# EasyEDA_Pro_Project_0_02.net
KiCad netlist of a schematic drawn in EasyEDA Pro
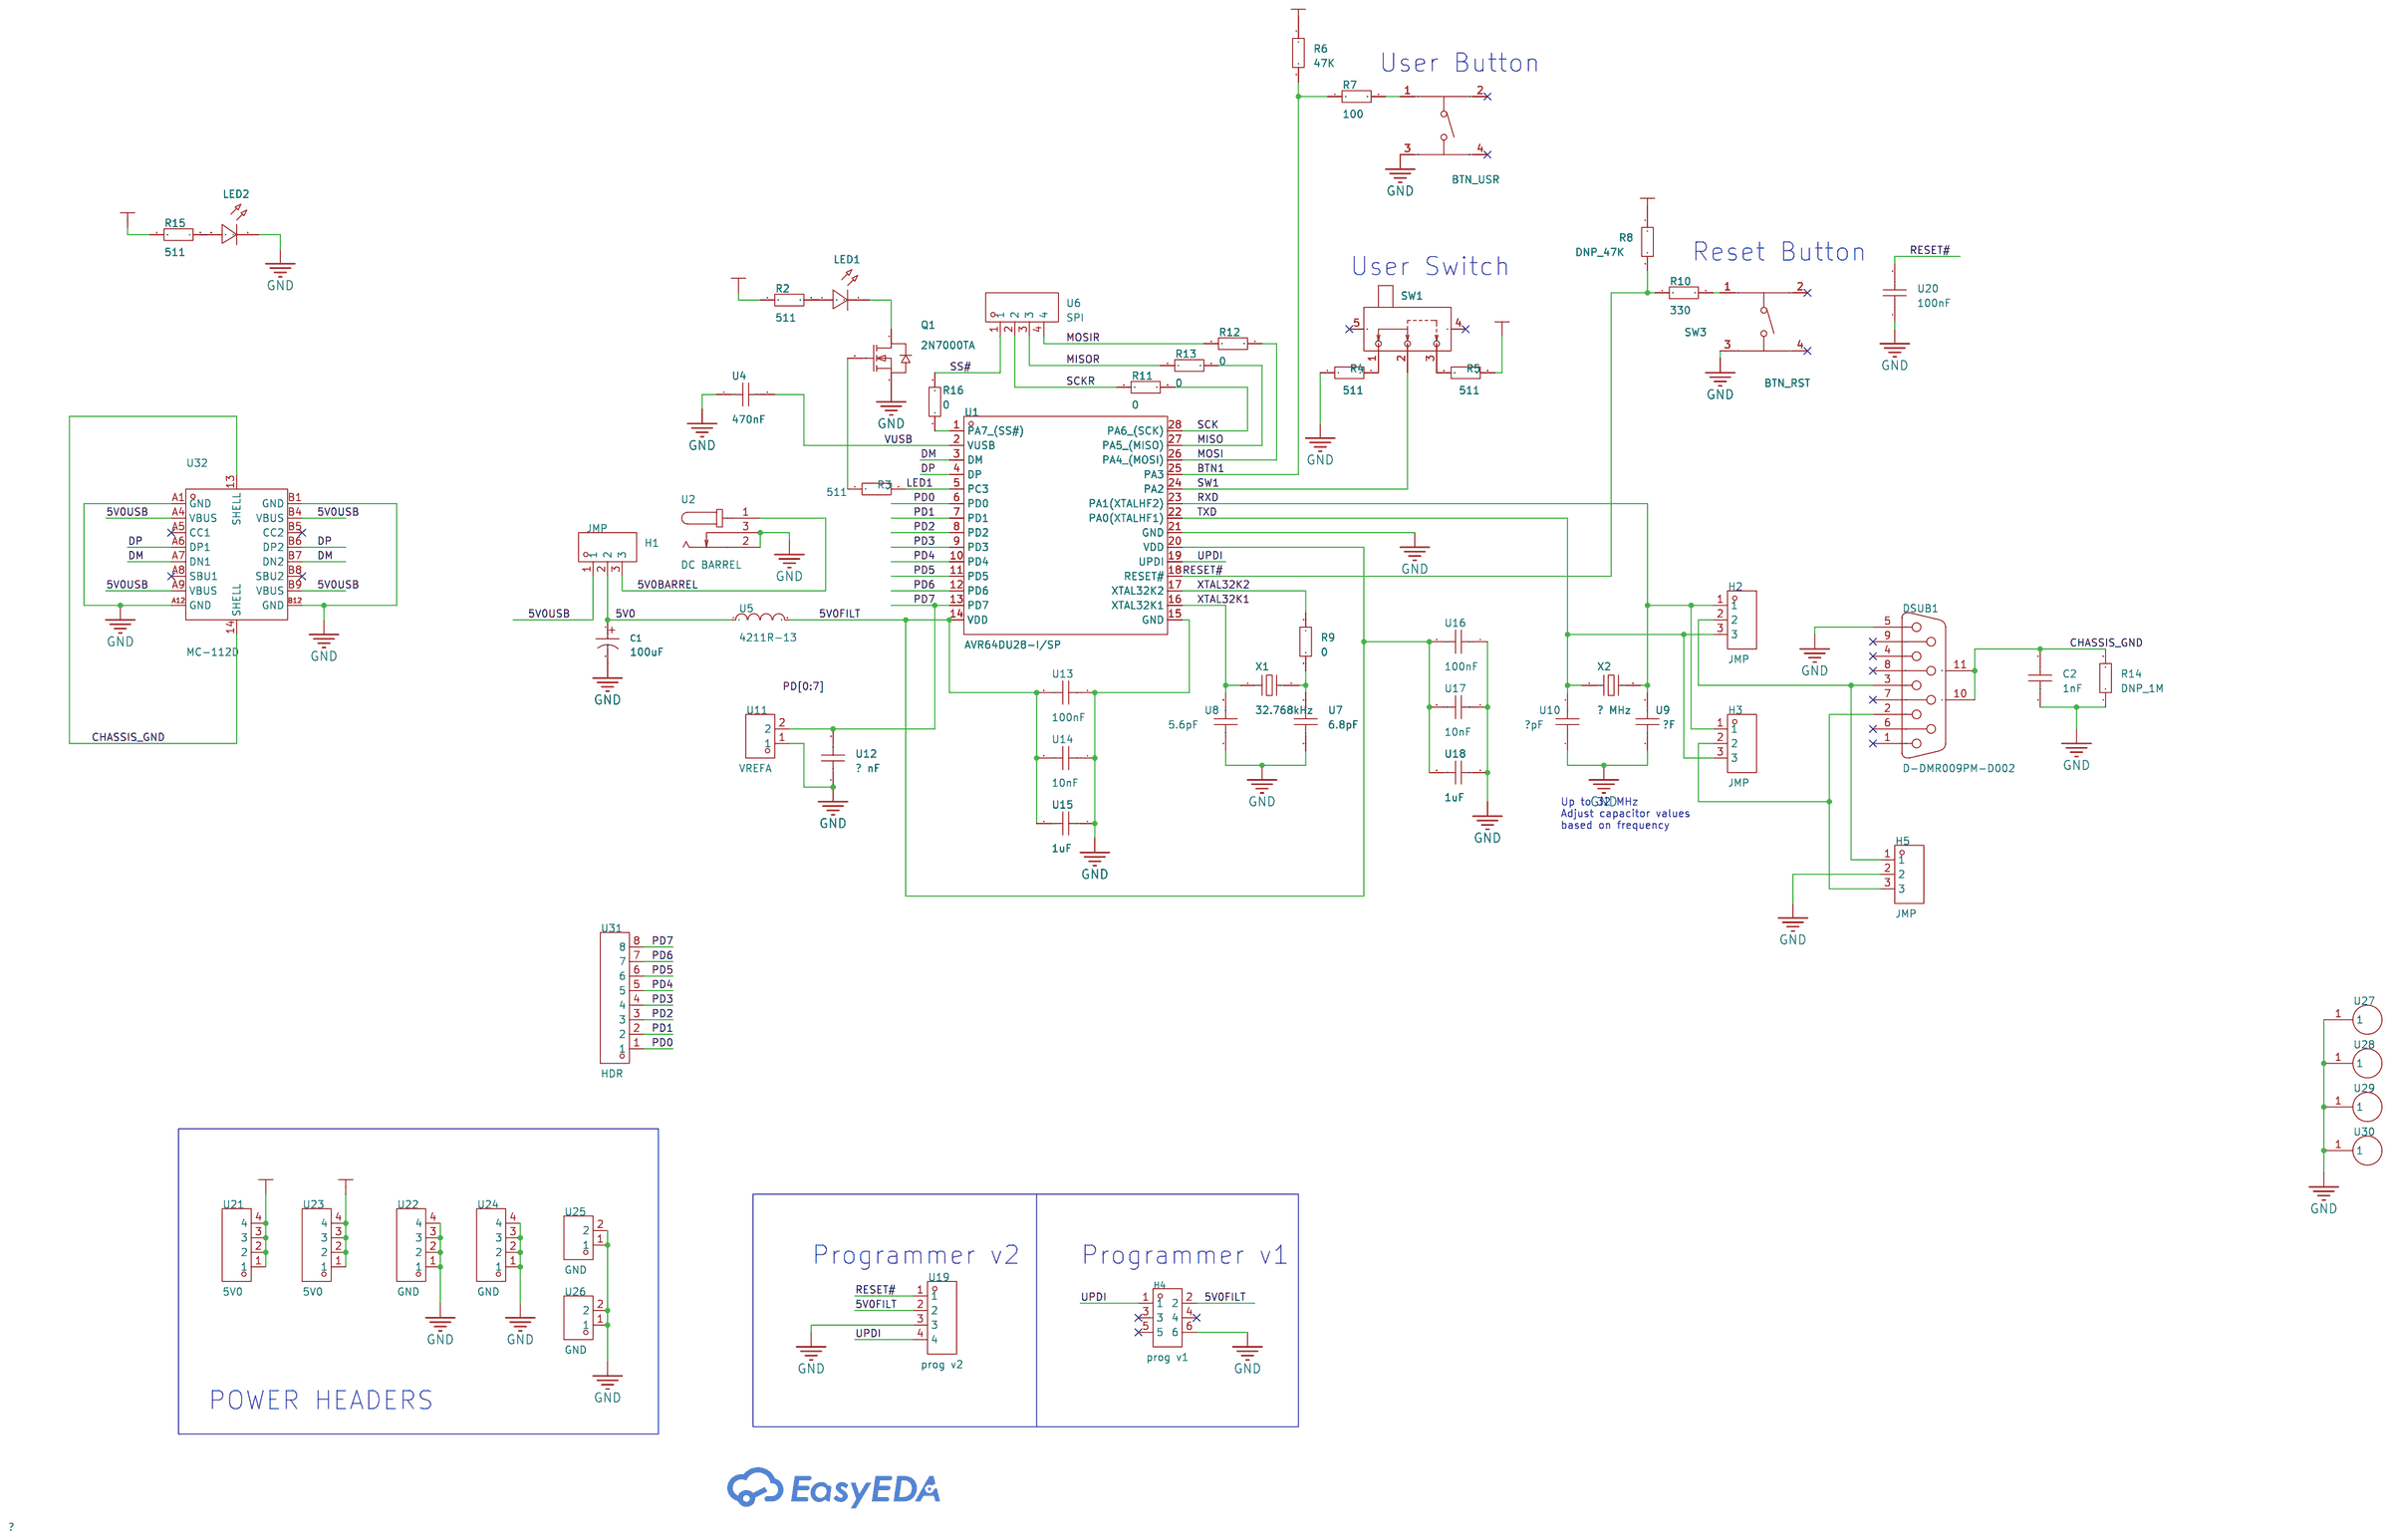
[diagram p0: schematic sheet]

(export (version "E")
  (design (tool "Eeschema 10.0.6"))
  (components
    (comp (ref "BTN_USR")
      (value "GT-TC075B-H070-L1")
      (footprint "easyedapro:KEY-TH_4P-L4.5-W4.5-P3.00-LS5.8")
      (fields (field (name "Manufacturer") "G-Switch(品赞)"))
      (libsource (lib "easyedapro") (part "GT-TC075B-H070-L1"))
    )
    (comp (ref "C1")
      (value "100uF")
      (footprint "easyedapro:CAP-TH_BD5.0-P2.00-D0.8-FD")
      (fields
        (field (name "Manufacturer Part") "KS107M010D07RR0VH2FP0")
        (field (name "Manufacturer") "CX(承兴)")
      )
      (libsource (lib "easyedapro") (part "100uF 10V 5*7"))
    )
    (comp (ref "C2")
      (value "1nF")
      (footprint "easyedapro:CAP-TH_L6.0-W3.5-P7.50-D1.0")
      (fields (field (name "Manufacturer Part") "Y25E1E102M") (field (name "Manufacturer") "HEL(鸿志)"))
      (libsource (lib "easyedapro") (part "Y25E1E102M"))
    )
    (comp (ref "DSUB1")
      (value "D-DMR009PM-D002")
      (footprint "easyedapro:DSUB-TH_DMR-9P")
      (fields (field (name "Manufacturer") "Ckmtw(灿科盟)"))
      (libsource (lib "easyedapro") (part "DMR-9P"))
    )
    (comp (ref "H1")
      (value "JMP")
      (footprint "easyedapro:HDR-TH_3P-P2.54-V-M-1")
      (fields (field (name "Manufacturer") "JILN(锦凌)"))
      (libsource (lib "easyedapro") (part "12251103CNG0S115001"))
    )
    (comp (ref "H2")
      (value "JMP")
      (footprint "easyedapro:HDR-TH_3P-P2.54-V-M-1")
      (fields (field (name "Manufacturer") "JILN(锦凌)"))
      (libsource (lib "easyedapro") (part "12251103CNG0S115001"))
    )
    (comp (ref "H3")
      (value "JMP")
      (footprint "easyedapro:HDR-TH_3P-P2.54-V-M-1")
      (fields (field (name "Manufacturer") "JILN(锦凌)"))
      (libsource (lib "easyedapro") (part "12251103CNG0S115001"))
    )
    (comp (ref "H4")
      (value "prog v1")
      (footprint "easyedapro:HDR-TH_6P-P2.54-V-M-R2-C3-S2.54")
      (fields (field (name "Manufacturer") "Liansheng(连盛)"))
      (libsource (lib "easyedapro") (part "PH-01291"))
    )
    (comp (ref "H5")
      (value "JMP")
      (footprint "easyedapro:HDR-TH_3P-P2.54-V-M-1")
      (fields (field (name "Manufacturer") "JILN(锦凌)"))
      (libsource (lib "easyedapro") (part "12251103CNG0S115001"))
    )
    (comp (ref "LED1")
      (value "~")
      (footprint "easyedapro:LED-TH_BD3.0-P2.54-FD")
      (libsource (lib "easyedapro") (part "LED_TH-R"))
    )
    (comp (ref "LED2")
      (value "~")
      (footprint "easyedapro:LED-TH_BD3.0-P2.54-FD")
      (libsource (lib "easyedapro") (part "LED_TH-R"))
    )
    (comp (ref "Q1")
      (value "2N7000TA")
      (footprint "easyedapro:TO-92-3_L4.8-W3.7-P2.54-L")
      (fields (field (name "Manufacturer") "onsemi(安森美)"))
      (libsource (lib "easyedapro") (part "2N7000TA"))
    )
    (comp (ref "R2")
      (value "511")
      (footprint "easyedapro:RES-TH_BD1.8-L3.2-P7.20-D0.4")
      (libsource (lib "easyedapro") (part "Res"))
    )
    (comp (ref "R3")
      (value "511")
      (footprint "easyedapro:RES-TH_BD1.8-L3.2-P7.20-D0.4")
      (libsource (lib "easyedapro") (part "Res"))
    )
    (comp (ref "R4")
      (value "511")
      (footprint "easyedapro:RES-TH_BD1.8-L3.2-P7.20-D0.4")
      (libsource (lib "easyedapro") (part "Res"))
    )
    (comp (ref "R5")
      (value "511")
      (footprint "easyedapro:RES-TH_BD1.8-L3.2-P7.20-D0.4")
      (libsource (lib "easyedapro") (part "Res"))
    )
    (comp (ref "R6")
      (value "47K")
      (footprint "easyedapro:RES-TH_BD1.8-L3.2-P7.20-D0.4")
      (libsource (lib "easyedapro") (part "Res"))
    )
    (comp (ref "R7")
      (value "100")
      (footprint "easyedapro:RES-TH_BD1.8-L3.2-P7.20-D0.4")
      (libsource (lib "easyedapro") (part "Res"))
    )
    (comp (ref "R8")
      (value "DNP_47K")
      (footprint "easyedapro:RES-TH_BD1.8-L3.2-P7.20-D0.4")
      (libsource (lib "easyedapro") (part "Res"))
    )
    (comp (ref "R9")
      (value "0")
      (footprint "easyedapro:RES-TH_BD1.8-L3.2-P7.20-D0.4")
      (libsource (lib "easyedapro") (part "Res"))
    )
    (comp (ref "R10")
      (value "330")
      (footprint "easyedapro:RES-TH_BD1.8-L3.2-P7.20-D0.4")
      (libsource (lib "easyedapro") (part "Res"))
    )
    (comp (ref "R11")
      (value "0")
      (footprint "easyedapro:RES-TH_BD1.8-L3.2-P7.20-D0.4")
      (libsource (lib "easyedapro") (part "Res"))
    )
    (comp (ref "R12")
      (value "0")
      (footprint "easyedapro:RES-TH_BD1.8-L3.2-P7.20-D0.4")
      (libsource (lib "easyedapro") (part "Res"))
    )
    (comp (ref "R13")
      (value "0")
      (footprint "easyedapro:RES-TH_BD1.8-L3.2-P7.20-D0.4")
      (libsource (lib "easyedapro") (part "Res"))
    )
    (comp (ref "R14")
      (value "DNP_1M")
      (footprint "easyedapro:RES-TH_BD1.8-L3.2-P7.20-D0.4")
      (libsource (lib "easyedapro") (part "Res"))
    )
    (comp (ref "R15")
      (value "511")
      (footprint "easyedapro:RES-TH_BD1.8-L3.2-P7.20-D0.4")
      (libsource (lib "easyedapro") (part "Res"))
    )
    (comp (ref "R16")
      (value "0")
      (footprint "easyedapro:RES-TH_BD1.8-L3.2-P7.20-D0.4")
      (libsource (lib "easyedapro") (part "Res"))
    )
    (comp (ref "SW1")
      (value "SS-12D07G4")
      (footprint "easyedapro:SW-TH_DEALON_SS-12D02-VGX")
      (fields (field (name "Manufacturer") "HanElectricity(瀚源)"))
      (libsource (lib "easyedapro") (part "SS-12D07G4"))
    )
    (comp (ref "SW3")
      (value "BTN_RST")
      (footprint "easyedapro:KEY-TH_4P-L4.5-W4.5-P3.00-LS5.8")
      (fields (field (name "Manufacturer") "G-Switch(品赞)"))
      (libsource (lib "easyedapro") (part "GT-TC075B-H070-L1"))
    )
    (comp (ref "U1")
      (value "AVR64DU28-I/SP")
      (footprint "easyedapro:SPDIP-28_L34.7-W7.2-P2.54-LS7.9-BL")
      (fields (field (name "Manufacturer") "MICROCHIP(美国微芯)"))
      (libsource (lib "easyedapro") (part "AVR64DB28-I/SP"))
    )
    (comp (ref "U2")
      (value "DC BARREL")
      (footprint "easyedapro:DC-IN-TH_DC-005-2.0_C22459640")
      (fields (field (name "Manufacturer") "HanElectricity(瀚源)"))
      (libsource (lib "easyedapro") (part "DC-005-2.0_C22459640"))
    )
    (comp (ref "U4")
      (value "470nF")
      (footprint "easyedapro:CAP-TH_L4.8-W2.4-P5.08-D0.6")
      (fields (field (name "Manufacturer Part") "178MU0009") (field (name "Manufacturer") "KNSCHA(科尼盛)"))
      (libsource (lib "easyedapro") (part "178MU0009"))
    )
    (comp (ref "U5")
      (value "4211R-13")
      (footprint "easyedapro:IND-TH_BD3.5-L4.4_4211R-13")
      (description "Impedance @ Frequency:50Ω@100MHz Circuits:1")
      (fields (field (name "Manufacturer") "API Delevan"))
      (libsource (lib "easyedapro") (part "4211R-13"))
    )
    (comp (ref "U6")
      (value "SPI")
      (footprint "easyedapro:HDR-TH_4P-P2.00-V-M")
      (fields (field (name "Manufacturer") "Yxcon(宇熙精密)"))
      (libsource (lib "easyedapro") (part "P220-1104A0BS087A1"))
    )
    (comp (ref "U7")
      (value "6.8pF")
      (footprint "easyedapro:CAP-TH_L4.8-W2.4-P5.08-D0.6")
      (fields (field (name "Manufacturer Part") "178MU0009") (field (name "Manufacturer") "KNSCHA(科尼盛)"))
      (libsource (lib "easyedapro") (part "178MU0009"))
    )
    (comp (ref "U8")
      (value "5.6pF")
      (footprint "easyedapro:CAP-TH_L4.8-W2.4-P5.08-D0.6")
      (fields (field (name "Manufacturer Part") "178MU0009") (field (name "Manufacturer") "KNSCHA(科尼盛)"))
      (libsource (lib "easyedapro") (part "178MU0009"))
    )
    (comp (ref "U9")
      (value "?F")
      (footprint "easyedapro:CAP-TH_L4.8-W2.4-P5.08-D0.6")
      (fields (field (name "Manufacturer Part") "178MU0009") (field (name "Manufacturer") "KNSCHA(科尼盛)"))
      (libsource (lib "easyedapro") (part "178MU0009"))
    )
    (comp (ref "U10")
      (value "?pF")
      (footprint "easyedapro:CAP-TH_L4.8-W2.4-P5.08-D0.6")
      (fields (field (name "Manufacturer Part") "178MU0009") (field (name "Manufacturer") "KNSCHA(科尼盛)"))
      (libsource (lib "easyedapro") (part "178MU0009"))
    )
    (comp (ref "U11")
      (value "VREFA")
      (footprint "easyedapro:HDR-TH_2P-P2.00-V-M")
      (fields (field (name "Manufacturer") "hanxia(韩下)"))
      (libsource (lib "easyedapro") (part "HX PZ2.0-1X2P ZZ"))
    )
    (comp (ref "U12")
      (value "? nF")
      (footprint "easyedapro:CAP-TH_L4.8-W2.4-P5.08-D0.6")
      (fields (field (name "Manufacturer Part") "178MU0009") (field (name "Manufacturer") "KNSCHA(科尼盛)"))
      (libsource (lib "easyedapro") (part "178MU0009"))
    )
    (comp (ref "U13")
      (value "100nF")
      (footprint "easyedapro:CAP-TH_L4.8-W2.4-P5.08-D0.6")
      (fields (field (name "Manufacturer Part") "178MU0009") (field (name "Manufacturer") "KNSCHA(科尼盛)"))
      (libsource (lib "easyedapro") (part "178MU0009"))
    )
    (comp (ref "U14")
      (value "10nF")
      (footprint "easyedapro:CAP-TH_L4.8-W2.4-P5.08-D0.6")
      (fields (field (name "Manufacturer Part") "178MU0009") (field (name "Manufacturer") "KNSCHA(科尼盛)"))
      (libsource (lib "easyedapro") (part "178MU0009"))
    )
    (comp (ref "U15")
      (value "1uF")
      (footprint "easyedapro:CAP-TH_L4.8-W2.4-P5.08-D0.6")
      (fields (field (name "Manufacturer Part") "178MU0009") (field (name "Manufacturer") "KNSCHA(科尼盛)"))
      (libsource (lib "easyedapro") (part "178MU0009"))
    )
    (comp (ref "U16")
      (value "100nF")
      (footprint "easyedapro:CAP-TH_L4.8-W2.4-P5.08-D0.6")
      (fields (field (name "Manufacturer Part") "178MU0009") (field (name "Manufacturer") "KNSCHA(科尼盛)"))
      (libsource (lib "easyedapro") (part "178MU0009"))
    )
    (comp (ref "U17")
      (value "10nF")
      (footprint "easyedapro:CAP-TH_L4.8-W2.4-P5.08-D0.6")
      (fields (field (name "Manufacturer Part") "178MU0009") (field (name "Manufacturer") "KNSCHA(科尼盛)"))
      (libsource (lib "easyedapro") (part "178MU0009"))
    )
    (comp (ref "U18")
      (value "1uF")
      (footprint "easyedapro:CAP-TH_L4.8-W2.4-P5.08-D0.6")
      (fields (field (name "Manufacturer Part") "178MU0009") (field (name "Manufacturer") "KNSCHA(科尼盛)"))
      (libsource (lib "easyedapro") (part "178MU0009"))
    )
    (comp (ref "U19")
      (value "prog v2")
      (footprint "easyedapro:HDR-TH_4P-P2.00-V-M")
      (fields (field (name "Manufacturer") "Yxcon(宇熙精密)"))
      (libsource (lib "easyedapro") (part "P220-1104A0BS087A1"))
    )
    (comp (ref "U20")
      (value "100nF")
      (footprint "easyedapro:CAP-TH_L4.8-W2.4-P5.08-D0.6")
      (fields (field (name "Manufacturer Part") "178MU0009") (field (name "Manufacturer") "KNSCHA(科尼盛)"))
      (libsource (lib "easyedapro") (part "178MU0009"))
    )
    (comp (ref "U21")
      (value "5V0")
      (footprint "easyedapro:HDR-TH_4P-P2.00-V-M")
      (fields (field (name "Manufacturer") "Yxcon(宇熙精密)"))
      (libsource (lib "easyedapro") (part "P220-1104A0BS087A1"))
    )
    (comp (ref "U22")
      (value "GND")
      (footprint "easyedapro:HDR-TH_4P-P2.00-V-M")
      (fields (field (name "Manufacturer") "Yxcon(宇熙精密)"))
      (libsource (lib "easyedapro") (part "P220-1104A0BS087A1"))
    )
    (comp (ref "U23")
      (value "5V0")
      (footprint "easyedapro:HDR-TH_4P-P2.00-V-M")
      (fields (field (name "Manufacturer") "Yxcon(宇熙精密)"))
      (libsource (lib "easyedapro") (part "P220-1104A0BS087A1"))
    )
    (comp (ref "U24")
      (value "GND")
      (footprint "easyedapro:HDR-TH_4P-P2.00-V-M")
      (fields (field (name "Manufacturer") "Yxcon(宇熙精密)"))
      (libsource (lib "easyedapro") (part "P220-1104A0BS087A1"))
    )
    (comp (ref "U25")
      (value "GND")
      (footprint "easyedapro:HDR-TH_2P-P2.00-V-M")
      (fields (field (name "Manufacturer") "hanxia(韩下)"))
      (libsource (lib "easyedapro") (part "HX PZ2.0-1X2P ZZ"))
    )
    (comp (ref "U26")
      (value "GND")
      (footprint "easyedapro:HDR-TH_2P-P2.00-V-M")
      (fields (field (name "Manufacturer") "hanxia(韩下)"))
      (libsource (lib "easyedapro") (part "HX PZ2.0-1X2P ZZ"))
    )
    (comp (ref "U27")
      (value "~")
      (footprint "easyedapro:Standoff 2.0mm")
      (libsource (lib "easyedapro") (part "Standoff 2.0mm"))
    )
    (comp (ref "U28")
      (value "~")
      (footprint "easyedapro:Standoff 2.0mm")
      (libsource (lib "easyedapro") (part "Standoff 2.0mm"))
    )
    (comp (ref "U29")
      (value "~")
      (footprint "easyedapro:Standoff 2.0mm")
      (libsource (lib "easyedapro") (part "Standoff 2.0mm"))
    )
    (comp (ref "U30")
      (value "~")
      (footprint "easyedapro:Standoff 2.0mm")
      (libsource (lib "easyedapro") (part "Standoff 2.0mm"))
    )
    (comp (ref "U31")
      (value "HDR")
      (footprint "easyedapro:HDR-TH_8P-P2.54-V-M")
      (fields (field (name "Manufacturer") "HANBO(汉博)"))
      (libsource (lib "easyedapro") (part "HB-PH3-25418PB2GOP"))
    )
    (comp (ref "U32")
      (value "MC-112D")
      (footprint "easyedapro:USB-C-TH_HANBO_MC-112D")
      (fields (field (name "Manufacturer") "HANBO(汉博)"))
      (libsource (lib "easyedapro") (part "MC-112D"))
    )
    (comp (ref "X1")
      (value "32.768kHz")
      (footprint "easyedapro:OSC-TH_BD2.0-P0.70-D0.3")
      (fields
        (field (name "Manufacturer Part") "TAXD32768K2BGBBZT2S")
        (field (name "Manufacturer") "YJX(雅晶鑫)")
      )
      (libsource (lib "easyedapro") (part "TAXD32768K2BGBBZT2S"))
    )
    (comp (ref "X2")
      (value "? MHz")
      (footprint "easyedapro:OSC-TH_BD2.0-P0.70-D0.3")
      (fields
        (field (name "Manufacturer Part") "TAXD32768K2BGBBZT2S")
        (field (name "Manufacturer") "YJX(雅晶鑫)")
      )
      (libsource (lib "easyedapro") (part "TAXD32768K2BGBBZT2S"))
    )
  )
  (nets
    (net (code "1") (name "/5V0BARREL") (class "Default")
      (node (ref "H1") (pin "3") (pinfunction "3_3") (pintype "unspecified"))
      (node (ref "U2") (pin "1") (pinfunction "1_1") (pintype "unspecified"))
    )
    (net (code "2") (name "/5V0FILT") (class "Default")
      (node (ref "H4") (pin "2") (pinfunction "2_2") (pintype "input"))
      (node (ref "U1") (pin "14") (pinfunction "VDD_14") (pintype "unspecified"))
      (node (ref "U1") (pin "20") (pinfunction "VDD_20") (pintype "unspecified"))
      (node (ref "U13") (pin "2") (pinfunction "2_2") (pintype "unspecified"))
      (node (ref "U14") (pin "2") (pinfunction "2_2") (pintype "unspecified"))
      (node (ref "U15") (pin "2") (pinfunction "2_2") (pintype "unspecified"))
      (node (ref "U16") (pin "2") (pinfunction "2_2") (pintype "unspecified"))
      (node (ref "U17") (pin "2") (pinfunction "2_2") (pintype "unspecified"))
      (node (ref "U18") (pin "2") (pinfunction "2_2") (pintype "unspecified"))
      (node (ref "U19") (pin "2") (pinfunction "2_2") (pintype "unspecified"))
      (node (ref "U5") (pin "2") (pinfunction "2_2") (pintype "unspecified"))
    )
    (net (code "3") (name "/5V0USB") (class "Default")
      (node (ref "H1") (pin "1") (pinfunction "1_1") (pintype "unspecified"))
      (node (ref "U32") (pin "A4") (pinfunction "VBUS_A4") (pintype "unspecified"))
      (node (ref "U32") (pin "A9") (pinfunction "VBUS_A9") (pintype "unspecified"))
      (node (ref "U32") (pin "B4") (pinfunction "VBUS_B4") (pintype "unspecified"))
      (node (ref "U32") (pin "B9") (pinfunction "VBUS_B9") (pintype "unspecified"))
    )
    (net (code "4") (name "/BTN1") (class "Default")
      (node (ref "R6") (pin "2") (pinfunction "2_2") (pintype "input"))
      (node (ref "R7") (pin "1") (pinfunction "1_1") (pintype "input"))
      (node (ref "U1") (pin "25") (pinfunction "PA3_25") (pintype "unspecified"))
    )
    (net (code "5") (name "/CHASSIS_GND") (class "Default")
      (node (ref "C2") (pin "1") (pinfunction "1_1") (pintype "input"))
      (node (ref "DSUB1") (pin "10") (pinfunction "MH1_10") (pintype "input"))
      (node (ref "DSUB1") (pin "11") (pinfunction "MH2_11") (pintype "input"))
      (node (ref "R14") (pin "2") (pinfunction "2_2") (pintype "input"))
      (node (ref "U32") (pin "13") (pinfunction "SHELL_13") (pintype "unspecified"))
      (node (ref "U32") (pin "14") (pinfunction "SHELL_14") (pintype "unspecified"))
    )
    (net (code "6") (name "/DM") (class "Default")
      (node (ref "U1") (pin "3") (pinfunction "DM_3") (pintype "unspecified"))
      (node (ref "U32") (pin "A7") (pinfunction "DN1_A7") (pintype "unspecified"))
      (node (ref "U32") (pin "B7") (pinfunction "DN2_B7") (pintype "unspecified"))
    )
    (net (code "7") (name "/DP") (class "Default")
      (node (ref "U1") (pin "4") (pinfunction "DP_4") (pintype "unspecified"))
      (node (ref "U32") (pin "A6") (pinfunction "DP1_A6") (pintype "unspecified"))
      (node (ref "U32") (pin "B6") (pinfunction "DP2_B6") (pintype "unspecified"))
    )
    (net (code "8") (name "/LED1") (class "Default")
      (node (ref "R3") (pin "2") (pinfunction "2_2") (pintype "input"))
      (node (ref "U1") (pin "5") (pinfunction "PC3_5") (pintype "unspecified"))
    )
    (net (code "9") (name "/MISO") (class "Default")
      (node (ref "R13") (pin "2") (pinfunction "2_2") (pintype "input"))
      (node (ref "U1") (pin "27") (pinfunction "PA5_(MISO)_27") (pintype "unspecified"))
    )
    (net (code "10") (name "/MISOR") (class "Default")
      (node (ref "R13") (pin "1") (pinfunction "1_1") (pintype "input"))
      (node (ref "U6") (pin "3") (pinfunction "3_3") (pintype "unspecified"))
    )
    (net (code "11") (name "/MOSI") (class "Default")
      (node (ref "R12") (pin "2") (pinfunction "2_2") (pintype "input"))
      (node (ref "U1") (pin "26") (pinfunction "PA4_(MOSI)_26") (pintype "unspecified"))
    )
    (net (code "12") (name "/MOSIR") (class "Default")
      (node (ref "R12") (pin "1") (pinfunction "1_1") (pintype "input"))
      (node (ref "U6") (pin "4") (pinfunction "4_4") (pintype "unspecified"))
    )
    (net (code "13") (name "/PD0") (class "Default")
      (node (ref "U1") (pin "6") (pinfunction "PD0_6") (pintype "unspecified"))
      (node (ref "U31") (pin "1") (pinfunction "1_1") (pintype "unspecified"))
    )
    (net (code "14") (name "/PD1") (class "Default")
      (node (ref "U1") (pin "7") (pinfunction "PD1_7") (pintype "unspecified"))
      (node (ref "U31") (pin "2") (pinfunction "2_2") (pintype "unspecified"))
    )
    (net (code "15") (name "/PD2") (class "Default")
      (node (ref "U1") (pin "8") (pinfunction "PD2_8") (pintype "unspecified"))
      (node (ref "U31") (pin "3") (pinfunction "3_3") (pintype "unspecified"))
    )
    (net (code "16") (name "/PD3") (class "Default")
      (node (ref "U1") (pin "9") (pinfunction "PD3_9") (pintype "unspecified"))
      (node (ref "U31") (pin "4") (pinfunction "4_4") (pintype "unspecified"))
    )
    (net (code "17") (name "/PD4") (class "Default")
      (node (ref "U1") (pin "10") (pinfunction "PD4_10") (pintype "unspecified"))
      (node (ref "U31") (pin "5") (pinfunction "5_5") (pintype "unspecified"))
    )
    (net (code "18") (name "/PD5") (class "Default")
      (node (ref "U1") (pin "11") (pinfunction "PD5_11") (pintype "unspecified"))
      (node (ref "U31") (pin "6") (pinfunction "6_6") (pintype "unspecified"))
    )
    (net (code "19") (name "/PD6") (class "Default")
      (node (ref "U1") (pin "12") (pinfunction "PD6_12") (pintype "unspecified"))
      (node (ref "U31") (pin "7") (pinfunction "7_7") (pintype "unspecified"))
    )
    (net (code "20") (name "/PD7") (class "Default")
      (node (ref "U1") (pin "13") (pinfunction "PD7_13") (pintype "unspecified"))
      (node (ref "U11") (pin "2") (pinfunction "2_2") (pintype "unspecified"))
      (node (ref "U12") (pin "2") (pinfunction "2_2") (pintype "unspecified"))
      (node (ref "U31") (pin "8") (pinfunction "8_8") (pintype "unspecified"))
    )
    (net (code "22") (name "/RESET#") (class "Default")
      (node (ref "R10") (pin "1") (pinfunction "1_1") (pintype "input"))
      (node (ref "R8") (pin "2") (pinfunction "2_2") (pintype "input"))
      (node (ref "U1") (pin "18") (pinfunction "RESET#_18") (pintype "unspecified"))
      (node (ref "U19") (pin "1") (pinfunction "1_1") (pintype "unspecified"))
      (node (ref "U20") (pin "2") (pinfunction "2_2") (pintype "unspecified"))
    )
    (net (code "23") (name "/RXD") (class "Default")
      (node (ref "H2") (pin "1") (pinfunction "1_1") (pintype "unspecified"))
      (node (ref "H3") (pin "1") (pinfunction "1_1") (pintype "unspecified"))
      (node (ref "U1") (pin "23") (pinfunction "PA1(XTALHF2)_23") (pintype "unspecified"))
      (node (ref "U9") (pin "2") (pinfunction "2_2") (pintype "unspecified"))
      (node (ref "X2") (pin "2") (pinfunction "2_2") (pintype "input"))
    )
    (net (code "24") (name "/SCK") (class "Default")
      (node (ref "R11") (pin "2") (pinfunction "2_2") (pintype "input"))
      (node (ref "U1") (pin "28") (pinfunction "PA6_(SCK)_28") (pintype "unspecified"))
    )
    (net (code "25") (name "/SCKR") (class "Default")
      (node (ref "R11") (pin "1") (pinfunction "1_1") (pintype "input"))
      (node (ref "U6") (pin "2") (pinfunction "2_2") (pintype "unspecified"))
    )
    (net (code "26") (name "/SS#") (class "Default")
      (node (ref "R16") (pin "2") (pinfunction "2_2") (pintype "input"))
      (node (ref "U6") (pin "1") (pinfunction "1_1") (pintype "unspecified"))
    )
    (net (code "27") (name "/SW1") (class "Default")
      (node (ref "SW1") (pin "2") (pinfunction "2_2") (pintype "unspecified"))
      (node (ref "U1") (pin "24") (pinfunction "PA2_24") (pintype "unspecified"))
    )
    (net (code "28") (name "/TXD") (class "Default")
      (node (ref "H2") (pin "3") (pinfunction "3_3") (pintype "unspecified"))
      (node (ref "H3") (pin "3") (pinfunction "3_3") (pintype "unspecified"))
      (node (ref "U1") (pin "22") (pinfunction "PA0(XTALHF1)_22") (pintype "unspecified"))
      (node (ref "U10") (pin "2") (pinfunction "2_2") (pintype "unspecified"))
      (node (ref "X2") (pin "1") (pinfunction "1_1") (pintype "input"))
    )
    (net (code "29") (name "/UPDI") (class "Default")
      (node (ref "H4") (pin "1") (pinfunction "1_1") (pintype "input"))
      (node (ref "U1") (pin "19") (pinfunction "UPDI_19") (pintype "unspecified"))
      (node (ref "U19") (pin "4") (pinfunction "4_4") (pintype "unspecified"))
    )
    (net (code "30") (name "/VUSB") (class "Default")
      (node (ref "U1") (pin "2") (pinfunction "VUSB_2") (pintype "unspecified"))
      (node (ref "U4") (pin "2") (pinfunction "2_2") (pintype "unspecified"))
    )
    (net (code "31") (name "/XTAL32K1") (class "Default")
      (node (ref "U1") (pin "16") (pinfunction "XTAL32K1_16") (pintype "unspecified"))
      (node (ref "U8") (pin "2") (pinfunction "2_2") (pintype "unspecified"))
      (node (ref "X1") (pin "1") (pinfunction "1_1") (pintype "input"))
    )
    (net (code "32") (name "/XTAL32K2") (class "Default")
      (node (ref "R9") (pin "1") (pinfunction "1_1") (pintype "input"))
      (node (ref "U1") (pin "17") (pinfunction "XTAL32K2_17") (pintype "unspecified"))
    )
    (net (code "33") (name "5V0") (class "Default")
      (node (ref "C1") (pin "1") (pinfunction "1_1") (pintype "input"))
      (node (ref "H1") (pin "2") (pinfunction "2_2") (pintype "unspecified"))
      (node (ref "R15") (pin "2") (pinfunction "2_2") (pintype "input"))
      (node (ref "R2") (pin "2") (pinfunction "2_2") (pintype "input"))
      (node (ref "R5") (pin "2") (pinfunction "2_2") (pintype "input"))
      (node (ref "R6") (pin "1") (pinfunction "1_1") (pintype "input"))
      (node (ref "R8") (pin "1") (pinfunction "1_1") (pintype "input"))
      (node (ref "U21") (pin "1") (pinfunction "1_1") (pintype "unspecified"))
      (node (ref "U21") (pin "2") (pinfunction "2_2") (pintype "unspecified"))
      (node (ref "U21") (pin "3") (pinfunction "3_3") (pintype "unspecified"))
      (node (ref "U21") (pin "4") (pinfunction "4_4") (pintype "unspecified"))
      (node (ref "U23") (pin "1") (pinfunction "1_1") (pintype "unspecified"))
      (node (ref "U23") (pin "2") (pinfunction "2_2") (pintype "unspecified"))
      (node (ref "U23") (pin "3") (pinfunction "3_3") (pintype "unspecified"))
      (node (ref "U23") (pin "4") (pinfunction "4_4") (pintype "unspecified"))
      (node (ref "U5") (pin "1") (pinfunction "1_1") (pintype "unspecified"))
    )
    (net (code "34") (name "GND") (class "Default")
      (node (ref "BTN_USR") (pin "3") (pinfunction "3_3") (pintype "unspecified"))
      (node (ref "C1") (pin "2") (pinfunction "2_2") (pintype "input"))
      (node (ref "C2") (pin "2") (pinfunction "2_2") (pintype "input"))
      (node (ref "DSUB1") (pin "5") (pinfunction "5_5") (pintype "input"))
      (node (ref "H4") (pin "6") (pinfunction "6_6") (pintype "input"))
      (node (ref "H5") (pin "2") (pinfunction "2_2") (pintype "unspecified"))
      (node (ref "LED2") (pin "2") (pinfunction "A_2") (pintype "input"))
      (node (ref "Q1") (pin "1") (pinfunction "S_1") (pintype "unspecified"))
      (node (ref "R14") (pin "1") (pinfunction "1_1") (pintype "input"))
      (node (ref "R4") (pin "1") (pinfunction "1_1") (pintype "input"))
      (node (ref "SW3") (pin "3") (pinfunction "3_3") (pintype "unspecified"))
      (node (ref "U1") (pin "15") (pinfunction "GND_15") (pintype "unspecified"))
      (node (ref "U1") (pin "21") (pinfunction "GND_21") (pintype "unspecified"))
      (node (ref "U10") (pin "1") (pinfunction "1_1") (pintype "unspecified"))
      (node (ref "U11") (pin "1") (pinfunction "1_1") (pintype "unspecified"))
      (node (ref "U12") (pin "1") (pinfunction "1_1") (pintype "unspecified"))
      (node (ref "U13") (pin "1") (pinfunction "1_1") (pintype "unspecified"))
      (node (ref "U14") (pin "1") (pinfunction "1_1") (pintype "unspecified"))
      (node (ref "U15") (pin "1") (pinfunction "1_1") (pintype "unspecified"))
      (node (ref "U16") (pin "1") (pinfunction "1_1") (pintype "unspecified"))
      (node (ref "U17") (pin "1") (pinfunction "1_1") (pintype "unspecified"))
      (node (ref "U18") (pin "1") (pinfunction "1_1") (pintype "unspecified"))
      (node (ref "U19") (pin "3") (pinfunction "3_3") (pintype "unspecified"))
      (node (ref "U2") (pin "2") (pinfunction "2_2") (pintype "unspecified"))
      (node (ref "U2") (pin "3") (pinfunction "3_3") (pintype "unspecified"))
      (node (ref "U20") (pin "1") (pinfunction "1_1") (pintype "unspecified"))
      (node (ref "U22") (pin "1") (pinfunction "1_1") (pintype "unspecified"))
      (node (ref "U22") (pin "2") (pinfunction "2_2") (pintype "unspecified"))
      (node (ref "U22") (pin "3") (pinfunction "3_3") (pintype "unspecified"))
      (node (ref "U22") (pin "4") (pinfunction "4_4") (pintype "unspecified"))
      (node (ref "U24") (pin "1") (pinfunction "1_1") (pintype "unspecified"))
      (node (ref "U24") (pin "2") (pinfunction "2_2") (pintype "unspecified"))
      (node (ref "U24") (pin "3") (pinfunction "3_3") (pintype "unspecified"))
      (node (ref "U24") (pin "4") (pinfunction "4_4") (pintype "unspecified"))
      (node (ref "U25") (pin "1") (pinfunction "1_1") (pintype "unspecified"))
      (node (ref "U25") (pin "2") (pinfunction "2_2") (pintype "unspecified"))
      (node (ref "U26") (pin "1") (pinfunction "1_1") (pintype "unspecified"))
      (node (ref "U26") (pin "2") (pinfunction "2_2") (pintype "unspecified"))
      (node (ref "U27") (pin "1") (pinfunction "1_1") (pintype "input"))
      (node (ref "U28") (pin "1") (pinfunction "1_1") (pintype "input"))
      (node (ref "U29") (pin "1") (pinfunction "1_1") (pintype "input"))
      (node (ref "U30") (pin "1") (pinfunction "1_1") (pintype "input"))
      (node (ref "U32") (pin "A1") (pinfunction "GND_A1") (pintype "unspecified"))
      (node (ref "U32") (pin "A12") (pinfunction "GND_A12") (pintype "unspecified"))
      (node (ref "U32") (pin "B1") (pinfunction "GND_B1") (pintype "unspecified"))
      (node (ref "U32") (pin "B12") (pinfunction "GND_B12") (pintype "unspecified"))
      (node (ref "U4") (pin "1") (pinfunction "1_1") (pintype "unspecified"))
      (node (ref "U7") (pin "1") (pinfunction "1_1") (pintype "unspecified"))
      (node (ref "U8") (pin "1") (pinfunction "1_1") (pintype "unspecified"))
      (node (ref "U9") (pin "1") (pinfunction "1_1") (pintype "unspecified"))
    )
    (net (code "35") (name "Net-(BTN_USR-Pad1)") (class "Default")
      (node (ref "BTN_USR") (pin "1") (pinfunction "1_1") (pintype "unspecified"))
      (node (ref "R7") (pin "2") (pinfunction "2_2") (pintype "input"))
    )
    (net (code "36") (name "Net-(DSUB1-Pad2)") (class "Default")
      (node (ref "DSUB1") (pin "2") (pinfunction "2_2") (pintype "input"))
      (node (ref "H3") (pin "2") (pinfunction "2_2") (pintype "unspecified"))
      (node (ref "H5") (pin "3") (pinfunction "3_3") (pintype "unspecified"))
    )
    (net (code "37") (name "Net-(DSUB1-Pad3)") (class "Default")
      (node (ref "DSUB1") (pin "3") (pinfunction "3_3") (pintype "input"))
      (node (ref "H2") (pin "2") (pinfunction "2_2") (pintype "unspecified"))
      (node (ref "H5") (pin "1") (pinfunction "1_1") (pintype "unspecified"))
    )
    (net (code "38") (name "Net-(LED1-A)") (class "Default")
      (node (ref "LED1") (pin "2") (pinfunction "A_2") (pintype "input"))
      (node (ref "Q1") (pin "3") (pinfunction "D_3") (pintype "unspecified"))
    )
    (net (code "39") (name "Net-(LED1-C)") (class "Default")
      (node (ref "LED1") (pin "1") (pinfunction "C_1") (pintype "input"))
      (node (ref "R2") (pin "1") (pinfunction "1_1") (pintype "input"))
    )
    (net (code "40") (name "Net-(LED2-C)") (class "Default")
      (node (ref "LED2") (pin "1") (pinfunction "C_1") (pintype "input"))
      (node (ref "R15") (pin "1") (pinfunction "1_1") (pintype "input"))
    )
    (net (code "41") (name "Net-(Q1-G)") (class "Default")
      (node (ref "Q1") (pin "2") (pinfunction "G_2") (pintype "unspecified"))
      (node (ref "R3") (pin "1") (pinfunction "1_1") (pintype "input"))
    )
    (net (code "42") (name "Net-(R4-Pad2)") (class "Default")
      (node (ref "R4") (pin "2") (pinfunction "2_2") (pintype "input"))
      (node (ref "SW1") (pin "1") (pinfunction "1_1") (pintype "unspecified"))
    )
    (net (code "43") (name "Net-(R5-Pad1)") (class "Default")
      (node (ref "R5") (pin "1") (pinfunction "1_1") (pintype "input"))
      (node (ref "SW1") (pin "3") (pinfunction "3_3") (pintype "unspecified"))
    )
    (net (code "44") (name "Net-(R9-Pad2)") (class "Default")
      (node (ref "R9") (pin "2") (pinfunction "2_2") (pintype "input"))
      (node (ref "U7") (pin "2") (pinfunction "2_2") (pintype "unspecified"))
      (node (ref "X1") (pin "2") (pinfunction "2_2") (pintype "input"))
    )
    (net (code "45") (name "Net-(R10-Pad2)") (class "Default")
      (node (ref "R10") (pin "2") (pinfunction "2_2") (pintype "input"))
      (node (ref "SW3") (pin "1") (pinfunction "1_1") (pintype "unspecified"))
    )
    (net (code "46") (name "Net-(U1-PA7_(SS#))") (class "Default")
      (node (ref "R16") (pin "1") (pinfunction "1_1") (pintype "input"))
      (node (ref "U1") (pin "1") (pinfunction "PA7_(SS#)_1") (pintype "unspecified"))
    )
    (net (code "47") (name "unconnected-(BTN_USR-Pad2)") (class "Default")
      (node (ref "BTN_USR") (pin "2") (pinfunction "2_2") (pintype "unspecified+no_connect"))
    )
    (net (code "48") (name "unconnected-(BTN_USR-Pad4)") (class "Default")
      (node (ref "BTN_USR") (pin "4") (pinfunction "4_4") (pintype "unspecified+no_connect"))
    )
    (net (code "49") (name "unconnected-(DSUB1-Pad1)") (class "Default")
      (node (ref "DSUB1") (pin "1") (pinfunction "1_1") (pintype "input+no_connect"))
    )
    (net (code "50") (name "unconnected-(DSUB1-Pad4)") (class "Default")
      (node (ref "DSUB1") (pin "4") (pinfunction "4_4") (pintype "input+no_connect"))
    )
    (net (code "51") (name "unconnected-(DSUB1-Pad6)") (class "Default")
      (node (ref "DSUB1") (pin "6") (pinfunction "6_6") (pintype "input+no_connect"))
    )
    (net (code "52") (name "unconnected-(DSUB1-Pad7)") (class "Default")
      (node (ref "DSUB1") (pin "7") (pinfunction "7_7") (pintype "input+no_connect"))
    )
    (net (code "53") (name "unconnected-(DSUB1-Pad8)") (class "Default")
      (node (ref "DSUB1") (pin "8") (pinfunction "8_8") (pintype "input+no_connect"))
    )
    (net (code "54") (name "unconnected-(DSUB1-Pad9)") (class "Default")
      (node (ref "DSUB1") (pin "9") (pinfunction "9_9") (pintype "input+no_connect"))
    )
    (net (code "55") (name "unconnected-(H4-Pad3)") (class "Default")
      (node (ref "H4") (pin "3") (pinfunction "3_3") (pintype "input+no_connect"))
    )
    (net (code "56") (name "unconnected-(H4-Pad4)") (class "Default")
      (node (ref "H4") (pin "4") (pinfunction "4_4") (pintype "input+no_connect"))
    )
    (net (code "57") (name "unconnected-(H4-Pad5)") (class "Default")
      (node (ref "H4") (pin "5") (pinfunction "5_5") (pintype "input+no_connect"))
    )
    (net (code "58") (name "unconnected-(SW1-Pad4)") (class "Default")
      (node (ref "SW1") (pin "4") (pinfunction "4_4") (pintype "unspecified+no_connect"))
    )
    (net (code "59") (name "unconnected-(SW1-Pad5)") (class "Default")
      (node (ref "SW1") (pin "5") (pinfunction "5_5") (pintype "unspecified+no_connect"))
    )
    (net (code "60") (name "unconnected-(SW3-Pad2)") (class "Default")
      (node (ref "SW3") (pin "2") (pinfunction "2_2") (pintype "unspecified+no_connect"))
    )
    (net (code "61") (name "unconnected-(SW3-Pad4)") (class "Default")
      (node (ref "SW3") (pin "4") (pinfunction "4_4") (pintype "unspecified+no_connect"))
    )
    (net (code "62") (name "unconnected-(U32-CC1-PadA5)") (class "Default")
      (node (ref "U32") (pin "A5") (pinfunction "CC1_A5") (pintype "unspecified+no_connect"))
    )
    (net (code "63") (name "unconnected-(U32-CC2-PadB5)") (class "Default")
      (node (ref "U32") (pin "B5") (pinfunction "CC2_B5") (pintype "unspecified+no_connect"))
    )
    (net (code "64") (name "unconnected-(U32-SBU1-PadA8)") (class "Default")
      (node (ref "U32") (pin "A8") (pinfunction "SBU1_A8") (pintype "unspecified+no_connect"))
    )
    (net (code "65") (name "unconnected-(U32-SBU2-PadB8)") (class "Default")
      (node (ref "U32") (pin "B8") (pinfunction "SBU2_B8") (pintype "unspecified+no_connect"))
    )
  )
)
